# sink_iref_gen.net
KiCad netlist of a schematic drawn in Altium Designer
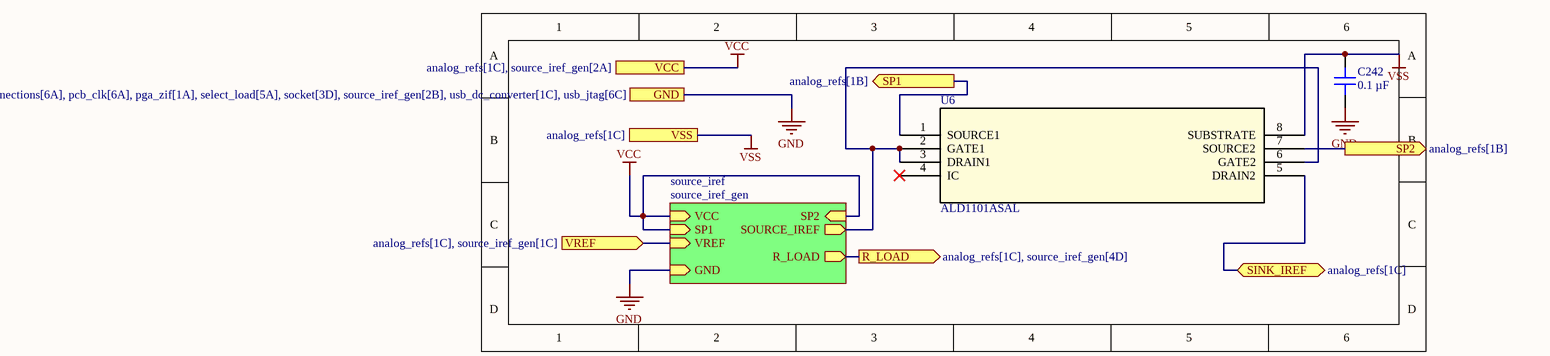
[diagram p0: sink_iref_gen.SchDoc]

(export (version "E")
  (design (tool "Eeschema 10.0.6"))
  (components
    (comp (ref "C242")
      (value "0.1 µF")
      (footprint "CAP 0805_2012")
      (description "CAP CER 0.1UF 16V X7R 0805")
      (fields
        (field (name "PART NUMBER") "160R15W104KV4T")
        (field (name "CAPACITANCE") "0.1 µF")
        (field (name "MANUFACTURER") "Johanson Dielectrics Inc.")
      )
      (libsource (lib "Celestial Altium Library - altium_library") (part "Capacitor"))
    )
    (comp (ref "U6")
      (value "ALD1101ASAL")
      (footprint "8-SOIC_ALD")
      (description "No Description Available")
      (fields (field (name "COPYRIGHT") "Copyright (C) 2026 Ultra Librarian. All rights reserved."))
      (libsource (lib "Mosfets") (part "ALD1101ASAL"))
    )
  )
  (nets
    (net (code "2") (name "/SINK_IREF") (class "Default")
      (node (ref "U6") (pin "5") (pinfunction "DRAIN2_5") (pintype "passive"))
    )
    (net (code "3") (name "/SOURCE_IREF") (class "Default")
      (node (ref "U6") (pin "2") (pinfunction "GATE1_2") (pintype "passive"))
      (node (ref "U6") (pin "3") (pinfunction "DRAIN1_3") (pintype "passive"))
      (node (ref "U6") (pin "6") (pinfunction "GATE2_6") (pintype "passive"))
    )
    (net (code "4") (name "/SP1") (class "Default")
      (node (ref "U6") (pin "1") (pinfunction "SOURCE1_1") (pintype "passive"))
    )
    (net (code "5") (name "/SP2") (class "Default")
      (node (ref "U6") (pin "7") (pinfunction "SOURCE2_7") (pintype "passive"))
    )
    (net (code "7") (name "GND") (class "Default")
      (node (ref "C242") (pin "1") (pinfunction "1_1") (pintype "passive"))
    )
    (net (code "9") (name "VSS") (class "Default")
      (node (ref "C242") (pin "2") (pinfunction "2_2") (pintype "passive"))
      (node (ref "U6") (pin "8") (pinfunction "SUBSTRATE_8") (pintype "passive"))
    )
    (net (code "10") (name "unconnected-(U6-IC-Pad4)") (class "Default")
      (node (ref "U6") (pin "4") (pinfunction "IC_4") (pintype "passive+no_connect"))
    )
  )
)
